# SH8_-_LOAD_MONITORING_2.net
KiCad netlist of a schematic drawn in Altium Designer
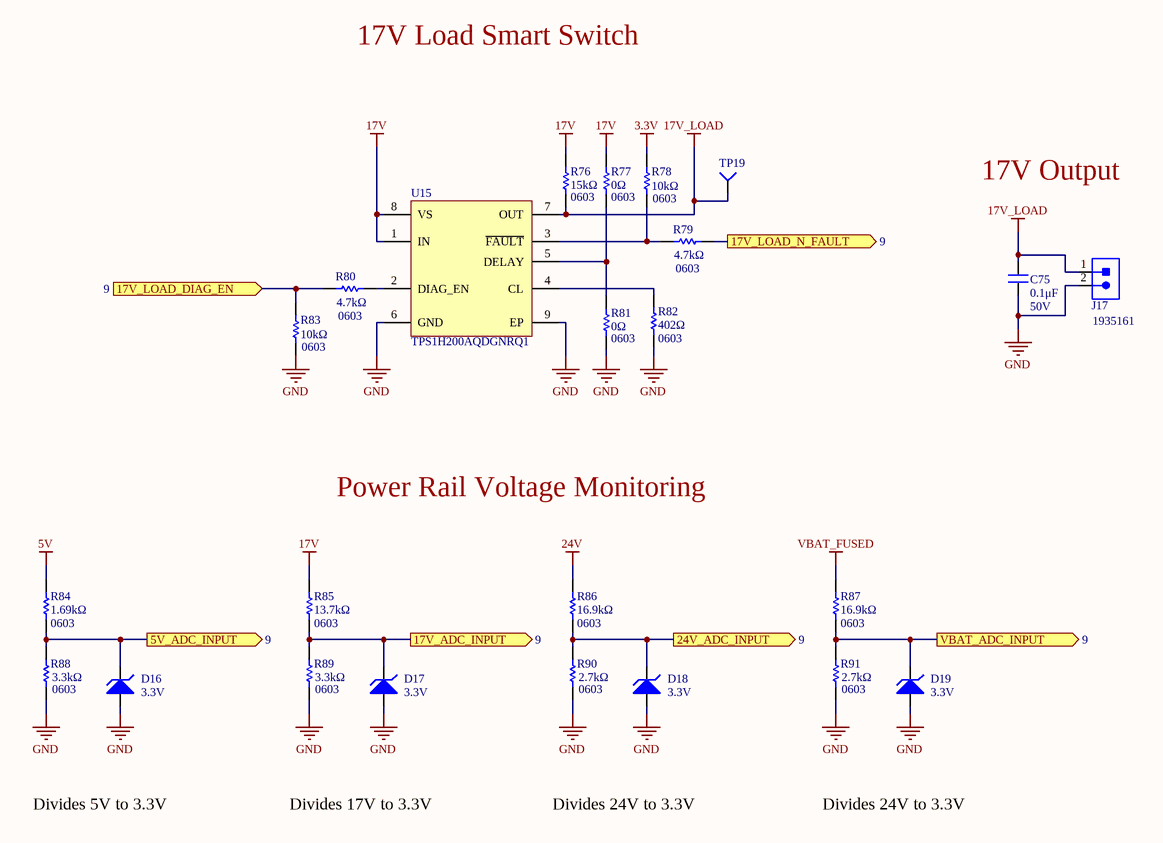
[diagram p0: SH8 - LOAD MONITORING 2.SchDoc]

(export (version "E")
  (design (tool "Eeschema 10.0.6"))
  (components
    (comp (ref "C75")
      (value "0.1μF")
      (footprint "CAP2012")
      (description "CAP CER 0.1UF 50V X7R 0805")
      (fields (field (name "TOLERANCE") "10%") (field (name "VOLTAGE RATING") "50V"))
      (libsource (lib "UWRT_Schematic_Library_2020") (part "CAP_0.1uF_50V_0805"))
    )
    (comp (ref "D16")
      (value "ESD5Z3.3T1G")
      (footprint "SOD523_UNI")
      (description "ESD5Z3.3T1G,SOD523 ESD DIODE < AZ")
      (fields (field (name "REVERSE STANDOFF VOLTAGE") "3.3V"))
      (libsource (lib "UWRT_Schematic_Library_2020") (part "ESD5Z3.3T1G"))
    )
    (comp (ref "D17")
      (value "ESD5Z3.3T1G")
      (footprint "SOD523_UNI")
      (description "ESD5Z3.3T1G,SOD523 ESD DIODE < AZ")
      (fields (field (name "REVERSE STANDOFF VOLTAGE") "3.3V"))
      (libsource (lib "UWRT_Schematic_Library_2020") (part "ESD5Z3.3T1G"))
    )
    (comp (ref "D18")
      (value "ESD5Z3.3T1G")
      (footprint "SOD523_UNI")
      (description "ESD5Z3.3T1G,SOD523 ESD DIODE < AZ")
      (fields (field (name "REVERSE STANDOFF VOLTAGE") "3.3V"))
      (libsource (lib "UWRT_Schematic_Library_2020") (part "ESD5Z3.3T1G"))
    )
    (comp (ref "D19")
      (value "ESD5Z3.3T1G")
      (footprint "SOD523_UNI")
      (description "ESD5Z3.3T1G,SOD523 ESD DIODE < AZ")
      (fields (field (name "REVERSE STANDOFF VOLTAGE") "3.3V"))
      (libsource (lib "UWRT_Schematic_Library_2020") (part "ESD5Z3.3T1G"))
    )
    (comp (ref "J17")
      (value "1935161")
      (footprint "1935161")
      (description "TERM BLK 2POS SIDE ENTRY 5MM")
      (fields (field (name "VOLTAGE") "300V") (field (name "MANUFACTURER PART NUMBER 1") "1935161"))
      (libsource (lib "UWRT_Schematic_Library_2020") (part "CON_2M_TERM"))
    )
    (comp (ref "R76")
      (value "15kΩ")
      (footprint "RESC0603(1608)_N")
      (description "RES 15K OHM 5% 1/10W 0603")
      (fields
        (field (name "TOLERANCE") "5%")
        (field (name "CASE CODE (IMPERIAL)") "0603")
        (field (name "Comment") "RES_15kΩ_0603")
      )
      (libsource (lib "UWRT_Schematic_Library_2020") (part "RES_15kΩ_0603_5%"))
    )
    (comp (ref "R77")
      (value "0Ω")
      (footprint "RESC0603(1608)_N")
      (description "RES 0 OHM JUMPER 1/10W 0603")
      (fields (field (name "CASE CODE (IMPERIAL)") "0603") (field (name "Comment") "RES_0Ω_0603"))
      (libsource (lib "UWRT_Schematic_Library_2020") (part "RES_0Ω_0603"))
    )
    (comp (ref "R78")
      (value "10kΩ")
      (footprint "RESC0603(1608)_N")
      (description "RES 10K OHM 5% 1/10W 0603")
      (fields
        (field (name "TOLERANCE") "5%")
        (field (name "CASE CODE (IMPERIAL)") "0603")
        (field (name "Comment") "RES_10kΩ_0603")
      )
      (libsource (lib "UWRT_Schematic_Library_2020") (part "RES_10kΩ_0603_5%"))
    )
    (comp (ref "R79")
      (value "4.7kΩ")
      (footprint "RESC0603(1608)_N")
      (description "RES 4.7K OHM 5% 1/10W 0603")
      (fields
        (field (name "TOLERANCE") "5%")
        (field (name "CASE CODE (IMPERIAL)") "0603")
        (field (name "Comment") "RES_4.7kΩ_0603")
      )
      (libsource (lib "UWRT_Schematic_Library_2020") (part "RES_4.7kΩ_0603_5%"))
    )
    (comp (ref "R80")
      (value "4.7kΩ")
      (footprint "RESC0603(1608)_N")
      (description "RES 4.7K OHM 5% 1/10W 0603")
      (fields
        (field (name "TOLERANCE") "5%")
        (field (name "CASE CODE (IMPERIAL)") "0603")
        (field (name "Comment") "RES_4.7kΩ_0603")
      )
      (libsource (lib "UWRT_Schematic_Library_2020") (part "RES_4.7kΩ_0603_5%"))
    )
    (comp (ref "R81")
      (value "0Ω")
      (footprint "RESC0603(1608)_N")
      (description "RES 0 OHM JUMPER 1/10W 0603")
      (fields (field (name "CASE CODE (IMPERIAL)") "0603") (field (name "Comment") "RES_0Ω_0603"))
      (libsource (lib "UWRT_Schematic_Library_2020") (part "RES_0Ω_0603"))
    )
    (comp (ref "R82")
      (value "RES_402Ω_0603")
      (footprint "RESC0603(1608)_N")
      (description "RES 402 OHM 0.5% 1/10W 0603")
      (fields
        (field (name "TOLERANCE") "0.5%")
        (field (name "RESISTANCE") "402Ω")
        (field (name "CASE CODE (IMPERIAL)") "0603")
      )
      (libsource (lib "UWRT_Schematic_Library_2020") (part "RES_402Ω_0603_0.5%"))
    )
    (comp (ref "R83")
      (value "10kΩ")
      (footprint "RESC0603(1608)_N")
      (description "RES 10K OHM 5% 1/10W 0603")
      (fields
        (field (name "TOLERANCE") "5%")
        (field (name "CASE CODE (IMPERIAL)") "0603")
        (field (name "Comment") "RES_10kΩ_0603")
      )
      (libsource (lib "UWRT_Schematic_Library_2020") (part "RES_10kΩ_0603_5%"))
    )
    (comp (ref "R84")
      (value "1.69kΩ")
      (footprint "RESC0603(1608)_N")
      (description "RES SMD 1.69K OHM 1% 1/10W 0603")
      (fields
        (field (name "TOLERANCE") "1%")
        (field (name "CASE CODE (IMPERIAL)") "0603")
        (field (name "Comment") "RES_1.69kΩ_0603")
      )
      (libsource (lib "UWRT_Schematic_Library_2020") (part "RES_1.69kΩ_0603_1%"))
    )
    (comp (ref "R85")
      (value "13.7kΩ")
      (footprint "RESC0603(1608)_N")
      (description "RES SMD 13.7K OHM 1% 1/10W 0603")
      (fields
        (field (name "TOLERANCE") "1%")
        (field (name "CASE CODE (IMPERIAL)") "0603")
        (field (name "Comment") "RES_13.7kΩ_0603")
      )
      (libsource (lib "UWRT_Schematic_Library_2020") (part "RES_13.7kΩ_0603_1%"))
    )
    (comp (ref "R86")
      (value "16.9kΩ")
      (footprint "RESC0603(1608)_N")
      (description "RES SMD 16.9K OHM 1% 1/10W 0603")
      (fields
        (field (name "TOLERANCE") "1%")
        (field (name "CASE CODE (IMPERIAL)") "0603")
        (field (name "Comment") "RES_16.9kΩ_0603")
      )
      (libsource (lib "UWRT_Schematic_Library_2020") (part "RES_16.9kΩ_0603_1%"))
    )
    (comp (ref "R87")
      (value "16.9kΩ")
      (footprint "RESC0603(1608)_N")
      (description "RES SMD 16.9K OHM 1% 1/10W 0603")
      (fields
        (field (name "TOLERANCE") "1%")
        (field (name "CASE CODE (IMPERIAL)") "0603")
        (field (name "Comment") "RES_16.9kΩ_0603")
      )
      (libsource (lib "UWRT_Schematic_Library_2020") (part "RES_16.9kΩ_0603_1%"))
    )
    (comp (ref "R88")
      (value "3.3kΩ")
      (footprint "RESC0603(1608)_N")
      (description "RES SMD 3.3K OHM 1% 1/10W 0603")
      (fields
        (field (name "TOLERANCE") "1%")
        (field (name "CASE CODE (IMPERIAL)") "0603")
        (field (name "Comment") "RES_3.3kΩ_0603")
      )
      (libsource (lib "UWRT_Schematic_Library_2020") (part "RES_3.3kΩ_0603_1%"))
    )
    (comp (ref "R89")
      (value "3.3kΩ")
      (footprint "RESC0603(1608)_N")
      (description "RES SMD 3.3K OHM 1% 1/10W 0603")
      (fields
        (field (name "TOLERANCE") "1%")
        (field (name "CASE CODE (IMPERIAL)") "0603")
        (field (name "Comment") "RES_3.3kΩ_0603")
      )
      (libsource (lib "UWRT_Schematic_Library_2020") (part "RES_3.3kΩ_0603_1%"))
    )
    (comp (ref "R90")
      (value "2.7kΩ")
      (footprint "RESC0603(1608)_N")
      (description "RES SMD 2.7K OHM 1% 1/10W 0603")
      (fields
        (field (name "TOLERANCE") "1%")
        (field (name "CASE CODE (IMPERIAL)") "0603")
        (field (name "Comment") "RES_2.7kΩ_0603")
      )
      (libsource (lib "UWRT_Schematic_Library_2020") (part "RES_2.7kΩ_0603_1%"))
    )
    (comp (ref "R91")
      (value "2.7kΩ")
      (footprint "RESC0603(1608)_N")
      (description "RES SMD 2.7K OHM 1% 1/10W 0603")
      (fields
        (field (name "TOLERANCE") "1%")
        (field (name "CASE CODE (IMPERIAL)") "0603")
        (field (name "Comment") "RES_2.7kΩ_0603")
      )
      (libsource (lib "UWRT_Schematic_Library_2020") (part "RES_2.7kΩ_0603_1%"))
    )
    (comp (ref "TP19")
      (value "TESTPOINT_1MM_CIRCLE")
      (footprint "TESTPOINT_CIRCLE_1MM")
      (description "TESTPOINT 1MM CIRCLE")
      (libsource (lib "UWRT_Schematic_Library_2020") (part "TESTPOINT_1MM_CIRCLE"))
    )
    (comp (ref "U15")
      (value "TPS1H200A-Q1")
      (footprint "DGN0008G")
      (description "IC PWR DRIVER N-CHAN 1:1 8MSOP")
      (fields (field (name "MANUFACTURER PART NUMBER 1") "TPS1H200AQDGNRQ1"))
      (libsource (lib "UWRT_Schematic_Library_2020") (part "TPS1H200A-Q1"))
    )
  )
  (nets
    (net (code "1") (name "/5V_ADC_INPUT") (class "Default")
      (node (ref "D16") (pin "2") (pinfunction "2_2") (pintype "passive"))
      (node (ref "R84") (pin "1") (pinfunction "1_1") (pintype "passive"))
      (node (ref "R88") (pin "2") (pinfunction "2_2") (pintype "passive"))
    )
    (net (code "2") (name "/17V_ADC_INPUT") (class "Default")
      (node (ref "D17") (pin "2") (pinfunction "2_2") (pintype "passive"))
      (node (ref "R85") (pin "1") (pinfunction "1_1") (pintype "passive"))
      (node (ref "R89") (pin "2") (pinfunction "2_2") (pintype "passive"))
    )
    (net (code "3") (name "/17V_LOAD_DIAG_EN") (class "Default")
      (node (ref "R80") (pin "1") (pinfunction "1_1") (pintype "passive"))
      (node (ref "R83") (pin "2") (pinfunction "2_2") (pintype "passive"))
    )
    (net (code "4") (name "/17V_LOAD_N_FAULT") (class "Default")
      (node (ref "R79") (pin "2") (pinfunction "2_2") (pintype "passive"))
    )
    (net (code "5") (name "/24V_ADC_INPUT") (class "Default")
      (node (ref "D18") (pin "2") (pinfunction "2_2") (pintype "passive"))
      (node (ref "R86") (pin "1") (pinfunction "1_1") (pintype "passive"))
      (node (ref "R90") (pin "2") (pinfunction "2_2") (pintype "passive"))
    )
    (net (code "6") (name "/VBAT_ADC_INPUT") (class "Default")
      (node (ref "D19") (pin "2") (pinfunction "2_2") (pintype "passive"))
      (node (ref "R87") (pin "1") (pinfunction "1_1") (pintype "passive"))
      (node (ref "R91") (pin "2") (pinfunction "2_2") (pintype "passive"))
    )
    (net (code "7") (name "3.3V") (class "Default")
      (node (ref "R78") (pin "2") (pinfunction "2_2") (pintype "passive"))
    )
    (net (code "8") (name "5V") (class "Default")
      (node (ref "R84") (pin "2") (pinfunction "2_2") (pintype "passive"))
    )
    (net (code "9") (name "17V") (class "Default")
      (node (ref "R76") (pin "2") (pinfunction "2_2") (pintype "passive"))
      (node (ref "R77") (pin "2") (pinfunction "2_2") (pintype "passive"))
      (node (ref "R85") (pin "2") (pinfunction "2_2") (pintype "passive"))
      (node (ref "U15") (pin "1") (pinfunction "IN_1") (pintype "passive"))
      (node (ref "U15") (pin "8") (pinfunction "VS_8") (pintype "passive"))
    )
    (net (code "10") (name "17V_LOAD") (class "Default")
      (node (ref "C75") (pin "2") (pinfunction "2_2") (pintype "passive"))
      (node (ref "J17") (pin "1") (pinfunction "1_1") (pintype "passive"))
      (node (ref "R76") (pin "1") (pinfunction "1_1") (pintype "passive"))
      (node (ref "TP19") (pin "1") (pinfunction "=value_1") (pintype "passive"))
      (node (ref "U15") (pin "7") (pinfunction "OUT_7") (pintype "passive"))
    )
    (net (code "11") (name "24V") (class "Default")
      (node (ref "R86") (pin "2") (pinfunction "2_2") (pintype "passive"))
    )
    (net (code "12") (name "GND") (class "Default")
      (node (ref "C75") (pin "1") (pinfunction "1_1") (pintype "passive"))
      (node (ref "D16") (pin "1") (pinfunction "1_1") (pintype "passive"))
      (node (ref "D17") (pin "1") (pinfunction "1_1") (pintype "passive"))
      (node (ref "D18") (pin "1") (pinfunction "1_1") (pintype "passive"))
      (node (ref "D19") (pin "1") (pinfunction "1_1") (pintype "passive"))
      (node (ref "J17") (pin "2") (pinfunction "2_2") (pintype "passive"))
      (node (ref "R81") (pin "1") (pinfunction "1_1") (pintype "passive"))
      (node (ref "R82") (pin "1") (pinfunction "1_1") (pintype "passive"))
      (node (ref "R83") (pin "1") (pinfunction "1_1") (pintype "passive"))
      (node (ref "R88") (pin "1") (pinfunction "1_1") (pintype "passive"))
      (node (ref "R89") (pin "1") (pinfunction "1_1") (pintype "passive"))
      (node (ref "R90") (pin "1") (pinfunction "1_1") (pintype "passive"))
      (node (ref "R91") (pin "1") (pinfunction "1_1") (pintype "passive"))
      (node (ref "U15") (pin "6") (pinfunction "GND_6") (pintype "passive"))
      (node (ref "U15") (pin "9") (pinfunction "EP_9") (pintype "passive"))
    )
    (net (code "13") (name "Net-(U15-CL)") (class "Default")
      (node (ref "R82") (pin "2") (pinfunction "2_2") (pintype "passive"))
      (node (ref "U15") (pin "4") (pinfunction "CL_4") (pintype "passive"))
    )
    (net (code "14") (name "Net-(U15-DELAY)") (class "Default")
      (node (ref "R77") (pin "1") (pinfunction "1_1") (pintype "passive"))
      (node (ref "R81") (pin "2") (pinfunction "2_2") (pintype "passive"))
      (node (ref "U15") (pin "5") (pinfunction "DELAY_5") (pintype "passive"))
    )
    (net (code "15") (name "Net-(U15-DIAG_EN)") (class "Default")
      (node (ref "R80") (pin "2") (pinfunction "2_2") (pintype "passive"))
      (node (ref "U15") (pin "2") (pinfunction "DIAG_EN_2") (pintype "passive"))
    )
    (net (code "16") (name "Net-(U15-~{FAULT})") (class "Default")
      (node (ref "R78") (pin "1") (pinfunction "1_1") (pintype "passive"))
      (node (ref "R79") (pin "1") (pinfunction "1_1") (pintype "passive"))
      (node (ref "U15") (pin "3") (pinfunction "~{FAULT}_3") (pintype "passive"))
    )
    (net (code "17") (name "VBAT_FUSED") (class "Default")
      (node (ref "R87") (pin "2") (pinfunction "2_2") (pintype "passive"))
    )
  )
)
